# 14_Power_DCIN.net
KiCad netlist of a schematic drawn in Altium Designer
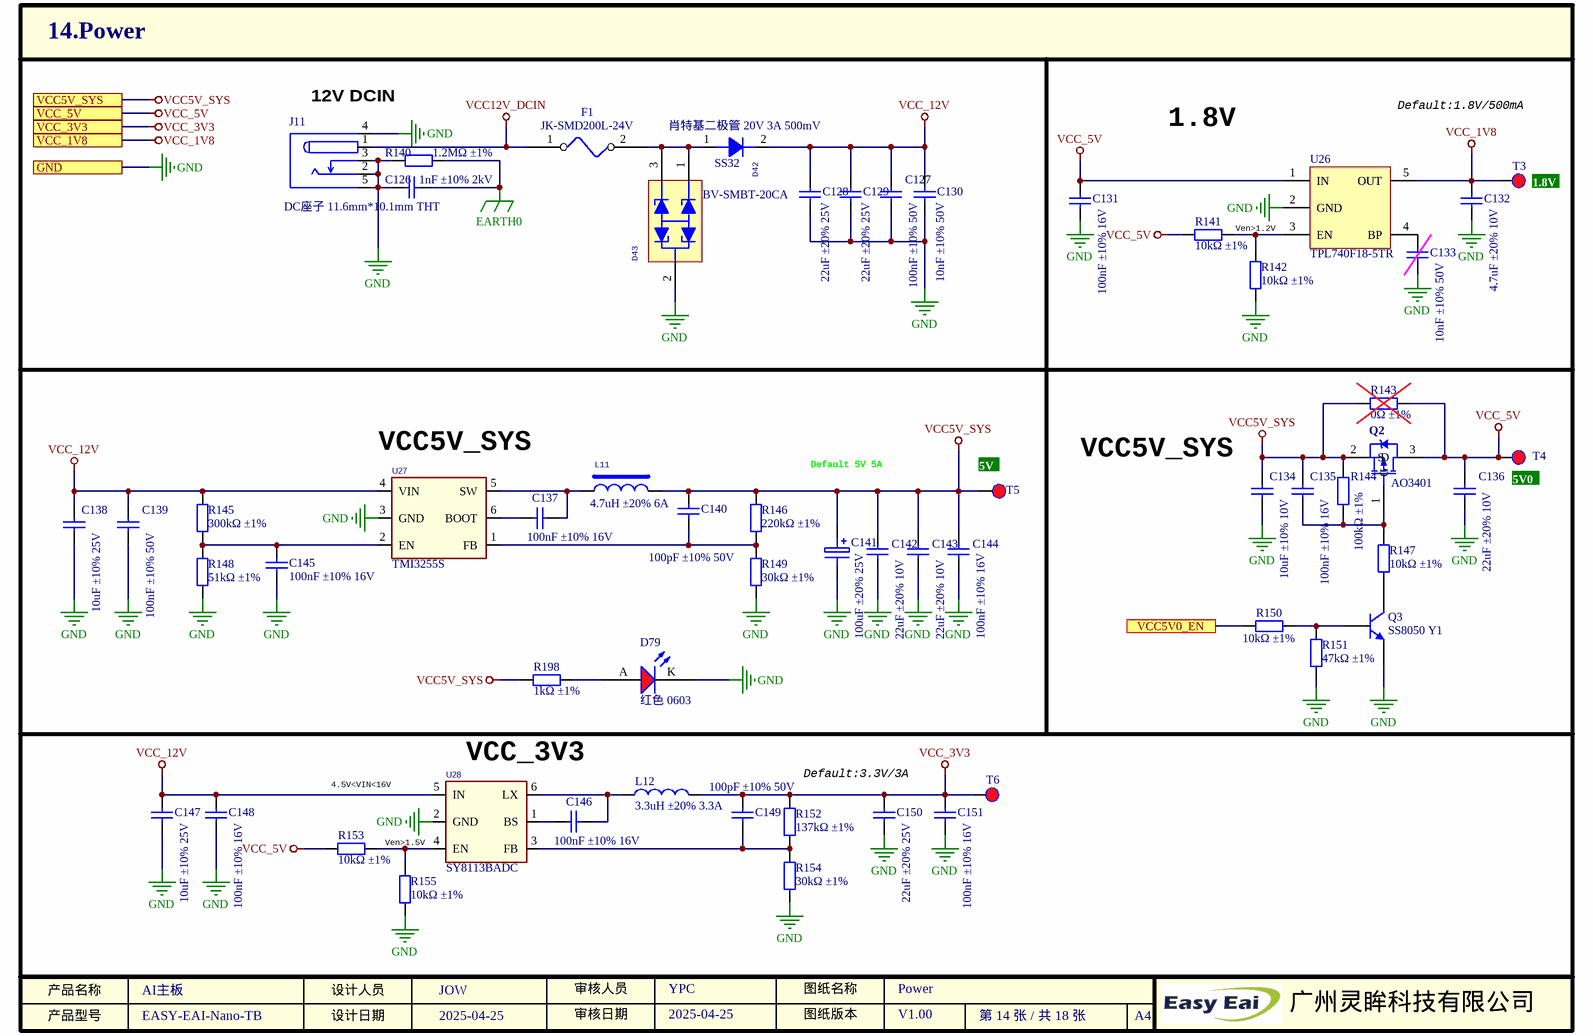
[diagram p0: 14.Power_DCIN.SchDoc]

(export (version "E")
  (design (tool "Eeschema 10.0.6"))
  (components
    (comp (ref "C126")
      (value "CC1206KKX7RDBB102")
      (footprint "1206_C")
      (description "SPZL000332")
      (fields (field (name "描述") "1nF ±10% 2kV"))
      (libsource (lib "altium-import") (part "root_0_1206 1nF ±10% 2kV_"))
    )
    (comp (ref "C127")
      (value "CC0603KRX7R9BB104")
      (footprint "0603_C")
      (description "SPZL000386")
      (fields (field (name "描述") "100nF ±10% 50V"))
      (libsource (lib "altium-import") (part "root_1_0603 100nF ±10% 50V_"))
    )
    (comp (ref "C128")
      (value "GRM21BR61E226ME44L")
      (footprint "0805_C")
      (description "SPZL000267")
      (fields (field (name "描述") "22uF ±20% 25V"))
      (libsource (lib "CAP_EASY-EAI") (part "0805 22uF ±20% 25V"))
    )
    (comp (ref "C129")
      (value "GRM21BR61E226ME44L")
      (footprint "0805_C")
      (description "SPZL000267")
      (fields (field (name "描述") "22uF ±20% 25V"))
      (libsource (lib "CAP_EASY-EAI") (part "0805 22uF ±20% 25V"))
    )
    (comp (ref "C130")
      (value "CL05B103KB5NNNC")
      (footprint "0402_C")
      (description "SPZL000342")
      (fields (field (name "描述") "10nF ±10% 50V"))
      (libsource (lib "CAP_EASY-EAI") (part "0402 10nF ±10% 50V"))
    )
    (comp (ref "C131")
      (value "CL05B104KO5NNNC")
      (footprint "0402_C")
      (description "SPZL000259")
      (fields (field (name "描述") "100nF ±10% 16V"))
      (libsource (lib "altium-import") (part "root_1_0402 100nF ±10% 16V_"))
    )
    (comp (ref "C132")
      (value "CL05A475MP5NRNC")
      (footprint "0402_C")
      (description "SPZL000339")
      (fields (field (name "描述") "4.7uF ±20% 10V"))
      (libsource (lib "altium-import") (part "root_1_0402 4.7uF ±20% 10V_"))
    )
    (comp (ref "C133")
      (value "NC/CL05B103KB5NNNC")
      (footprint "0402_C")
      (description "SPZL000342")
      (fields (field (name "描述") "10nF ±10% 50V"))
      (libsource (lib "altium-import") (part "root_1_0402 10nF ±10% 50V_"))
    )
    (comp (ref "C134")
      (value "CL10A106KP8NNNC")
      (footprint "0603_C")
      (description "SPZL000260")
      (fields (field (name "描述") "10uF ±10% 10V"))
      (libsource (lib "CAP_lexing") (part "0603 10uF ±10% 10V"))
    )
    (comp (ref "C135")
      (value "CL05B104KO5NNNC")
      (footprint "0402_C")
      (description "SPZL000259")
      (fields (field (name "描述") "100nF ±10% 16V"))
      (libsource (lib "CAP_lexing") (part "0402 100nF ±10% 16V"))
    )
    (comp (ref "C136")
      (value "CL10A226MP8NUNE")
      (footprint "0603_C")
      (description "SPZL000315")
      (fields (field (name "描述") "22uF ±20% 10V"))
      (libsource (lib "CAP_lexing") (part "0603 22uF ±20% 10V"))
    )
    (comp (ref "C137")
      (value "CL05B104KO5NNNC")
      (footprint "0402_C")
      (description "SPZL000259")
      (fields (field (name "描述") "100nF ±10% 16V"))
      (libsource (lib "altium-import") (part "root_0_0402 100nF ±10% 16V_"))
    )
    (comp (ref "C138")
      (value "GRM21BR61E106KA73L")
      (footprint "0805_C")
      (description "SPZL000262")
      (fields (field (name "描述") "10uF ±10% 25V"))
      (libsource (lib "altium-import") (part "root_1_0805 10uF ±10% 25V_"))
    )
    (comp (ref "C139")
      (value "CC0603KRX7R9BB104")
      (footprint "0603_C")
      (description "SPZL000386")
      (fields (field (name "描述") "100nF ±10% 50V"))
      (libsource (lib "altium-import") (part "root_1_0603 100nF ±10% 50V_"))
    )
    (comp (ref "C140")
      (value "CC0402KRX7R9BB101")
      (footprint "0402_C")
      (description "SPZL000312")
      (fields (field (name "描述") "100pF ±10% 50V"))
      (libsource (lib "altium-import") (part "root_1_0402 100pF ±10% 50V_"))
    )
    (comp (ref "C141")
      (value "RVT1E101M0607")
      (footprint "SMD,D6.3xL7.7mm")
      (description "SPZL000519")
      (fields (field (name "描述") "100uF ±20% 25V"))
      (libsource (lib "altium-import") (part "root_0_电解电容 100uF ±20% 25V_"))
    )
    (comp (ref "C142")
      (value "CL10A226MP8NUNE")
      (footprint "0603_C")
      (description "SPZL000315")
      (fields (field (name "描述") "22uF ±20% 10V"))
      (libsource (lib "altium-import") (part "root_1_0603 22uF ±20% 10V_"))
    )
    (comp (ref "C143")
      (value "CL10A226MP8NUNE")
      (footprint "0603_C")
      (description "SPZL000315")
      (fields (field (name "描述") "22uF ±20% 10V"))
      (libsource (lib "altium-import") (part "root_1_0603 22uF ±20% 10V_"))
    )
    (comp (ref "C144")
      (value "CL05B104KO5NNNC")
      (footprint "0402_C")
      (description "SPZL000259")
      (fields (field (name "描述") "100nF ±10% 16V"))
      (libsource (lib "altium-import") (part "root_1_0402 100nF ±10% 16V_"))
    )
    (comp (ref "C145")
      (value "CL05B104KO5NNNC")
      (footprint "0402_C")
      (description "SPZL000259")
      (fields (field (name "描述") "100nF ±10% 16V"))
      (libsource (lib "altium-import") (part "root_1_0402 100nF ±10% 16V_"))
    )
    (comp (ref "C146")
      (value "CL05B104KO5NNNC")
      (footprint "0402_C")
      (description "SPZL000259")
      (fields (field (name "描述") "100nF ±10% 16V"))
      (libsource (lib "altium-import") (part "root_0_0402 100nF ±10% 16V_"))
    )
    (comp (ref "C147")
      (value "GRM21BR61E106KA73L")
      (footprint "0805_C")
      (description "SPZL000262")
      (fields (field (name "描述") "10uF ±10% 25V"))
      (libsource (lib "altium-import") (part "root_1_0805 10uF ±10% 25V_"))
    )
    (comp (ref "C148")
      (value "CL05B104KO5NNNC")
      (footprint "0402_C")
      (description "SPZL000259")
      (fields (field (name "描述") "100nF ±10% 16V"))
      (libsource (lib "altium-import") (part "root_1_0402 100nF ±10% 16V_"))
    )
    (comp (ref "C149")
      (value "CC0402KRX7R9BB101")
      (footprint "0402_C")
      (description "SPZL000312")
      (fields (field (name "描述") "100pF ±10% 50V"))
      (libsource (lib "altium-import") (part "root_1_0402 100pF ±10% 50V_"))
    )
    (comp (ref "C150")
      (value "GRM21BR61E226ME44L")
      (footprint "0805_C")
      (description "SPZL000267")
      (fields (field (name "描述") "22uF ±20% 25V"))
      (libsource (lib "altium-import") (part "root_1_0805 22uF ±20% 25V_"))
    )
    (comp (ref "C151")
      (value "CL05B104KO5NNNC")
      (footprint "0402_C")
      (description "SPZL000259")
      (fields (field (name "描述") "100nF ±10% 16V"))
      (libsource (lib "altium-import") (part "root_1_0402 100nF ±10% 16V_"))
    )
    (comp (ref "D42")
      (value "肖特基二极管")
      (footprint "DO_214AC")
      (description "SPZL000094")
      (fields (field (name "描述") "肖特基二极管 20V 3A 500mV") (field (name "型号") "SS32"))
      (libsource (lib "Diode_EASY-EAI") (part "SS32"))
    )
    (comp (ref "D43")
      (value "BV-SMBT-20CA")
      (footprint "SMB-T_L5.4-W3.3-BI")
      (description "SPZL000611")
      (fields (field (name "型号") "BV-SMBT-20CA"))
      (libsource (lib "ESD_EASY-EAI") (part "TVS BV-SMBT-20CA"))
    )
    (comp (ref "D79")
      (value "红色 0603")
      (footprint "0603_LED_S1")
      (description "SPZL000214")
      (fields (field (name "描述") "红色 0603"))
      (libsource (lib "LED_EASY-EAI") (part "红色 0603"))
    )
    (comp (ref "F1")
      (value "JK-SMD200L-24V")
      (footprint "2920")
      (description "SPZL000105")
      (fields (field (name "型号") "JK-SMD200L-24V"))
      (libsource (lib "ESD_lexing") (part "自恢复保险丝 JK-SMD200L-24V"))
    )
    (comp (ref "J11")
      (value "DC-044A-20A")
      (footprint "DC-044A-20A")
      (description "SPZL000133")
      (fields (field (name "描述") "DC座子 11.6mm*10.1mm THT"))
      (libsource (lib "altium-import") (part "root_0_DC座子 11.6mm*10.1mm THT_"))
    )
    (comp (ref "L11")
      (value "MWSA0603S-4R7MT")
      (footprint "IND-SMD_L7.0-W6.6")
      (description "SPZL001133")
      (fields (field (name "描述") "4.7uH ±20% 6A"))
      (libsource (lib "Inductor_EASY-EAI") (part "4.7uH ±20% 6A"))
    )
    (comp (ref "L12")
      (value "SMNR4030-3R3MT")
      (footprint "IND-4.0*4.0*3.0")
      (description "SPZL000206")
      (fields (field (name "描述") "3.3uH ±20% 3.3A"))
      (libsource (lib "Inductor_EASY-EAI") (part "3.3uH ±20% 3.3A"))
    )
    (comp (ref "Q2")
      (value "AO3401")
      (footprint "SOT-23")
      (description "SPZL000800")
      (fields (field (name "型号") "AO3401"))
      (libsource (lib "MOS_lexing") (part "P沟道 AO3401"))
    )
    (comp (ref "Q3")
      (value "SS8050 Y1")
      (footprint "SOT-23(SOT-23-3)")
      (description "SPZL000089")
      (fields (field (name "型号") "SS8050 Y1"))
      (libsource (lib "MOS_lexing") (part "NPN SS8050 Y1"))
    )
    (comp (ref "R140")
      (value "1206W4F1204T5E")
      (footprint "1206_R")
      (description "SPZL000388")
      (fields (field (name "描述") "1.2MΩ ±1%"))
      (libsource (lib "RES_EASY-EAI") (part "1206 1.2MΩ ±1%"))
    )
    (comp (ref "R141")
      (value "0402WGF1002TCE")
      (footprint "0402_R")
      (description "SPZL000271")
      (fields (field (name "描述") "10kΩ ±1%"))
      (libsource (lib "") (part "0402 10kΩ ±1%_1"))
    )
    (comp (ref "R142")
      (value "0402WGF1002TCE")
      (footprint "0402_R")
      (description "SPZL000271")
      (fields (field (name "描述") "10kΩ ±1%"))
      (libsource (lib "RES_EASY-EAI") (part "0402 10kΩ ±1%"))
    )
    (comp (ref "R143")
      (value "NC/0805W8F0000T5E")
      (footprint "0805_R")
      (description "SPZL000350")
      (fields (field (name "描述") "0Ω ±1%"))
      (libsource (lib "RES_lexing") (part "0805 0Ω ±1%"))
    )
    (comp (ref "R144")
      (value "0402WGF1003TCE")
      (footprint "0402_R")
      (description "SPZL000282")
      (fields (field (name "描述") "100kΩ ±1%"))
      (libsource (lib "RES_lexing") (part "0402 100kΩ ±1%"))
    )
    (comp (ref "R145")
      (value "0402WGF3003TCE")
      (footprint "0402_R")
      (description "SPZL000393")
      (fields (field (name "描述") "300kΩ ±1%"))
      (libsource (lib "RES_EASY-EAI") (part "0402 300kΩ ±1%"))
    )
    (comp (ref "R146")
      (value "0402WGF2203TCE")
      (footprint "0402_R")
      (description "SPZL000877")
      (fields (field (name "描述") "220kΩ ±1%"))
      (libsource (lib "RES_EASY-EAI") (part "0402 220kΩ ±1%"))
    )
    (comp (ref "R147")
      (value "0402WGF1002TCE")
      (footprint "0402_R")
      (description "SPZL000271")
      (fields (field (name "描述") "10kΩ ±1%"))
      (libsource (lib "RES_lexing") (part "0402 10kΩ ±1%"))
    )
    (comp (ref "R148")
      (value "0402WGF5102TCE")
      (footprint "0402_R")
      (description "SPZL000788")
      (fields (field (name "描述") "51kΩ ±1%"))
      (libsource (lib "RES_EASY-EAI") (part "0402 51kΩ ±1%"))
    )
    (comp (ref "R149")
      (value "NQ02WGF3002TCE")
      (footprint "0402_R")
      (description "SPZL000323")
      (fields (field (name "描述") "30kΩ ±1%"))
      (libsource (lib "RES_EASY-EAI") (part "0402 30kΩ ±1%"))
    )
    (comp (ref "R150")
      (value "0402WGF1002TCE")
      (footprint "0402_R")
      (description "SPZL000271")
      (fields (field (name "描述") "10kΩ ±1%"))
      (libsource (lib "") (part "0402 10kΩ ±1%_1"))
    )
    (comp (ref "R151")
      (value "0402WGF4702TCE")
      (footprint "0402_R")
      (description "SPZL000348")
      (fields (field (name "描述") "47kΩ ±1%"))
      (libsource (lib "RES_lexing") (part "0402 47kΩ ±1%"))
    )
    (comp (ref "R152")
      (value "0402WGF1373TCE")
      (footprint "0402_R")
      (description "SPZL000322")
      (fields (field (name "描述") "137kΩ ±1%"))
      (libsource (lib "RES_EASY-EAI") (part "0402 137kΩ ±1%"))
    )
    (comp (ref "R153")
      (value "0402WGF1002TCE")
      (footprint "0402_R")
      (description "SPZL000271")
      (fields (field (name "描述") "10kΩ ±1%"))
      (libsource (lib "") (part "0402 10kΩ ±1%_1"))
    )
    (comp (ref "R154")
      (value "NQ02WGF3002TCE")
      (footprint "0402_R")
      (description "SPZL000323")
      (fields (field (name "描述") "30kΩ ±1%"))
      (libsource (lib "RES_EASY-EAI") (part "0402 30kΩ ±1%"))
    )
    (comp (ref "R155")
      (value "0402WGF1002TCE")
      (footprint "0402_R")
      (description "SPZL000271")
      (fields (field (name "描述") "10kΩ ±1%"))
      (libsource (lib "RES_EASY-EAI") (part "0402 10kΩ ±1%"))
    )
    (comp (ref "R198")
      (value "0402WGF1001TCE")
      (footprint "0402_R")
      (description "SPZL000275")
      (fields (field (name "描述") "1kΩ ±1%"))
      (libsource (lib "RES_EASY-EAI") (part "0402 1kΩ ±1%"))
    )
    (comp (ref "T3")
      (value "TEST-DOT")
      (footprint "PAD-25/40")
      (libsource (lib "Other_EASY-EAI") (part "TEST-DOT"))
    )
    (comp (ref "T4")
      (value "TEST-DOT")
      (footprint "PAD-25/40")
      (libsource (lib "Other_lexing") (part "TEST-DOT"))
    )
    (comp (ref "T5")
      (value "TEST-DOT")
      (footprint "PAD-25/40")
      (libsource (lib "Other_EASY-EAI") (part "TEST-DOT"))
    )
    (comp (ref "T6")
      (value "TEST-DOT")
      (footprint "PAD-25/40")
      (libsource (lib "Other_EASY-EAI") (part "TEST-DOT"))
    )
    (comp (ref "U26")
      (value "TPL740F18-5TR")
      (footprint "SOT-23-5")
      (description "SPZL000630")
      (fields (field (name "型号") "TPL740F18-5TR"))
      (libsource (lib "EASY-EAI-Nano-TB V1.01") (part "TPL740F18-5TR"))
    )
    (comp (ref "U27")
      (value "TMI3255S")
      (footprint "SOT23-6")
      (description "SPZL001130")
      (fields (field (name "型号") "TMI3255S"))
      (libsource (lib "Power_EASY-EAI") (part "TMI3255S"))
    )
    (comp (ref "U28")
      (value "SY8113BADC")
      (footprint "sot23-6")
      (description "SPZL000041")
      (fields (field (name "型号") "SY8113BADC"))
      (libsource (lib "Power_EASY-EAI") (part "SY8113BADC"))
    )
  )
  (nets
    (net (code "1") (name "/VCC5V0_EN") (class "Default")
      (node (ref "R150") (pin "1") (pinfunction "1_1") (pintype "passive"))
    )
    (net (code "2") (name "EARTH0") (class "Default")
      (node (ref "C126") (pin "2") (pinfunction "2_2") (pintype "passive"))
      (node (ref "R140") (pin "2") (pinfunction "2_2") (pintype "passive"))
    )
    (net (code "3") (name "GND") (class "Default")
      (node (ref "C126") (pin "1") (pinfunction "1_1") (pintype "passive"))
      (node (ref "C127") (pin "1") (pinfunction "1_1") (pintype "passive"))
      (node (ref "C128") (pin "1") (pinfunction "1_1") (pintype "passive"))
      (node (ref "C129") (pin "1") (pinfunction "1_1") (pintype "passive"))
      (node (ref "C130") (pin "1") (pinfunction "1_1") (pintype "passive"))
      (node (ref "C131") (pin "1") (pinfunction "1_1") (pintype "passive"))
      (node (ref "C132") (pin "1") (pinfunction "1_1") (pintype "passive"))
      (node (ref "C133") (pin "1") (pinfunction "1_1") (pintype "passive"))
      (node (ref "C134") (pin "1") (pinfunction "1_1") (pintype "passive"))
      (node (ref "C136") (pin "1") (pinfunction "1_1") (pintype "passive"))
      (node (ref "C138") (pin "1") (pinfunction "1_1") (pintype "passive"))
      (node (ref "C139") (pin "1") (pinfunction "1_1") (pintype "passive"))
      (node (ref "C141") (pin "2") (pinfunction "2_2") (pintype "passive"))
      (node (ref "C142") (pin "1") (pinfunction "1_1") (pintype "passive"))
      (node (ref "C143") (pin "1") (pinfunction "1_1") (pintype "passive"))
      (node (ref "C144") (pin "1") (pinfunction "1_1") (pintype "passive"))
      (node (ref "C145") (pin "1") (pinfunction "1_1") (pintype "passive"))
      (node (ref "C147") (pin "1") (pinfunction "1_1") (pintype "passive"))
      (node (ref "C148") (pin "1") (pinfunction "1_1") (pintype "passive"))
      (node (ref "C150") (pin "1") (pinfunction "1_1") (pintype "passive"))
      (node (ref "C151") (pin "1") (pinfunction "1_1") (pintype "passive"))
      (node (ref "D43") (pin "2") (pintype "passive"))
      (node (ref "D79") (pin "K") (pinfunction "K_K") (pintype "passive"))
      (node (ref "J11") (pin "2") (pinfunction "2_2") (pintype "power_in"))
      (node (ref "J11") (pin "3") (pinfunction "3_3") (pintype "power_in"))
      (node (ref "J11") (pin "4") (pinfunction "4_4") (pintype "power_in"))
      (node (ref "J11") (pin "5") (pinfunction "5_5") (pintype "power_in"))
      (node (ref "Q3") (pin "2") (pinfunction "E_2") (pintype "passive"))
      (node (ref "R140") (pin "1") (pinfunction "1_1") (pintype "passive"))
      (node (ref "R142") (pin "1") (pinfunction "1_1") (pintype "passive"))
      (node (ref "R148") (pin "1") (pinfunction "1_1") (pintype "passive"))
      (node (ref "R149") (pin "1") (pinfunction "1_1") (pintype "passive"))
      (node (ref "R151") (pin "1") (pinfunction "1_1") (pintype "passive"))
      (node (ref "R154") (pin "1") (pinfunction "1_1") (pintype "passive"))
      (node (ref "R155") (pin "1") (pinfunction "1_1") (pintype "passive"))
      (node (ref "U26") (pin "2") (pinfunction "GND_2") (pintype "passive"))
      (node (ref "U27") (pin "3") (pinfunction "GND_3") (pintype "passive"))
      (node (ref "U28") (pin "2") (pinfunction "GND_2") (pintype "passive"))
    )
    (net (code "4") (name "Net-(D42-A)") (class "Default")
      (node (ref "D42") (pin "1") (pinfunction "A_1") (pintype "passive"))
      (node (ref "D43") (pin "1") (pintype "passive"))
      (node (ref "D43") (pin "3") (pintype "passive"))
      (node (ref "F1") (pin "2") (pinfunction "2_2") (pintype "passive"))
    )
    (net (code "5") (name "Net-(D79-PadA)") (class "Default")
      (node (ref "D79") (pin "A") (pinfunction "A_A") (pintype "passive"))
      (node (ref "R198") (pin "2") (pinfunction "2_2") (pintype "passive"))
    )
    (net (code "6") (name "Net-(Q2-G)") (class "Default")
      (node (ref "C135") (pin "1") (pinfunction "1_1") (pintype "passive"))
      (node (ref "Q2") (pin "1") (pinfunction "G_1") (pintype "passive"))
      (node (ref "R144") (pin "1") (pinfunction "1_1") (pintype "passive"))
      (node (ref "R147") (pin "2") (pinfunction "2_2") (pintype "passive"))
    )
    (net (code "7") (name "Net-(Q3-B)") (class "Default")
      (node (ref "Q3") (pin "1") (pinfunction "B_1") (pintype "passive"))
      (node (ref "R150") (pin "2") (pinfunction "2_2") (pintype "passive"))
      (node (ref "R151") (pin "2") (pinfunction "2_2") (pintype "passive"))
    )
    (net (code "8") (name "Net-(Q3-C)") (class "Default")
      (node (ref "Q3") (pin "3") (pinfunction "C_3") (pintype "passive"))
      (node (ref "R147") (pin "1") (pinfunction "1_1") (pintype "passive"))
    )
    (net (code "9") (name "Net-(U26-BP)") (class "Default")
      (node (ref "C133") (pin "2") (pinfunction "2_2") (pintype "passive"))
      (node (ref "U26") (pin "4") (pinfunction "BP_4") (pintype "passive"))
    )
    (net (code "10") (name "Net-(U26-EN)") (class "Default")
      (node (ref "R141") (pin "2") (pinfunction "2_2") (pintype "passive"))
      (node (ref "R142") (pin "2") (pinfunction "2_2") (pintype "passive"))
      (node (ref "U26") (pin "3") (pinfunction "EN_3") (pintype "passive"))
    )
    (net (code "11") (name "Net-(U27-BOOT)") (class "Default")
      (node (ref "C137") (pin "1") (pinfunction "1_1") (pintype "passive"))
      (node (ref "U27") (pin "6") (pinfunction "BOOT_6") (pintype "passive"))
    )
    (net (code "12") (name "Net-(U27-EN)") (class "Default")
      (node (ref "C145") (pin "2") (pinfunction "2_2") (pintype "passive"))
      (node (ref "R145") (pin "1") (pinfunction "1_1") (pintype "passive"))
      (node (ref "R148") (pin "2") (pinfunction "2_2") (pintype "passive"))
      (node (ref "U27") (pin "2") (pinfunction "EN_2") (pintype "passive"))
    )
    (net (code "13") (name "Net-(U27-FB)") (class "Default")
      (node (ref "C140") (pin "1") (pinfunction "1_1") (pintype "passive"))
      (node (ref "R146") (pin "1") (pinfunction "1_1") (pintype "passive"))
      (node (ref "R149") (pin "2") (pinfunction "2_2") (pintype "passive"))
      (node (ref "U27") (pin "1") (pinfunction "FB_1") (pintype "passive"))
    )
    (net (code "14") (name "Net-(U27-SW)") (class "Default")
      (node (ref "C137") (pin "2") (pinfunction "2_2") (pintype "passive"))
      (node (ref "L11") (pin "1") (pinfunction "1_1") (pintype "passive"))
      (node (ref "U27") (pin "5") (pinfunction "SW_5") (pintype "passive"))
    )
    (net (code "15") (name "Net-(U28-BS)") (class "Default")
      (node (ref "C146") (pin "1") (pinfunction "1_1") (pintype "passive"))
      (node (ref "U28") (pin "1") (pinfunction "BS_1") (pintype "passive"))
    )
    (net (code "16") (name "Net-(U28-EN)") (class "Default")
      (node (ref "R153") (pin "2") (pinfunction "2_2") (pintype "passive"))
      (node (ref "R155") (pin "2") (pinfunction "2_2") (pintype "passive"))
      (node (ref "U28") (pin "4") (pinfunction "EN_4") (pintype "passive"))
    )
    (net (code "17") (name "Net-(U28-FB)") (class "Default")
      (node (ref "C149") (pin "1") (pinfunction "1_1") (pintype "passive"))
      (node (ref "R152") (pin "1") (pinfunction "1_1") (pintype "passive"))
      (node (ref "R154") (pin "2") (pinfunction "2_2") (pintype "passive"))
      (node (ref "U28") (pin "3") (pinfunction "FB_3") (pintype "passive"))
    )
    (net (code "18") (name "Net-(U28-LX)") (class "Default")
      (node (ref "C146") (pin "2") (pinfunction "2_2") (pintype "passive"))
      (node (ref "L12") (pin "1") (pinfunction "1_1") (pintype "passive"))
      (node (ref "U28") (pin "6") (pinfunction "LX_6") (pintype "passive"))
    )
    (net (code "19") (name "VCC5V_SYS") (class "Default")
      (node (ref "C134") (pin "2") (pinfunction "2_2") (pintype "passive"))
      (node (ref "C135") (pin "2") (pinfunction "2_2") (pintype "passive"))
      (node (ref "C140") (pin "2") (pinfunction "2_2") (pintype "passive"))
      (node (ref "C141") (pin "1") (pinfunction "1_1") (pintype "passive"))
      (node (ref "C142") (pin "2") (pinfunction "2_2") (pintype "passive"))
      (node (ref "C143") (pin "2") (pinfunction "2_2") (pintype "passive"))
      (node (ref "C144") (pin "2") (pinfunction "2_2") (pintype "passive"))
      (node (ref "L11") (pin "2") (pinfunction "2_2") (pintype "passive"))
      (node (ref "Q2") (pin "2") (pinfunction "S_2") (pintype "passive"))
      (node (ref "R143") (pin "1") (pinfunction "1_1") (pintype "passive"))
      (node (ref "R144") (pin "2") (pinfunction "2_2") (pintype "passive"))
      (node (ref "R146") (pin "2") (pinfunction "2_2") (pintype "passive"))
      (node (ref "R198") (pin "1") (pinfunction "1_1") (pintype "passive"))
      (node (ref "T5") (pin "1") (pinfunction "1_1") (pintype "passive"))
    )
    (net (code "20") (name "VCC12V_DCIN") (class "Default")
      (node (ref "F1") (pin "1") (pinfunction "1_1") (pintype "passive"))
      (node (ref "J11") (pin "1") (pinfunction "1_1") (pintype "power_in"))
    )
    (net (code "21") (name "VCC_1V8") (class "Default")
      (node (ref "C132") (pin "2") (pinfunction "2_2") (pintype "passive"))
      (node (ref "T3") (pin "1") (pinfunction "1_1") (pintype "passive"))
      (node (ref "U26") (pin "5") (pinfunction "OUT_5") (pintype "passive"))
    )
    (net (code "22") (name "VCC_3V3") (class "Default")
      (node (ref "C149") (pin "2") (pinfunction "2_2") (pintype "passive"))
      (node (ref "C150") (pin "2") (pinfunction "2_2") (pintype "passive"))
      (node (ref "C151") (pin "2") (pinfunction "2_2") (pintype "passive"))
      (node (ref "L12") (pin "2") (pinfunction "2_2") (pintype "passive"))
      (node (ref "R152") (pin "2") (pinfunction "2_2") (pintype "passive"))
      (node (ref "T6") (pin "1") (pinfunction "1_1") (pintype "passive"))
    )
    (net (code "23") (name "VCC_5V") (class "Default")
      (node (ref "C131") (pin "2") (pinfunction "2_2") (pintype "passive"))
      (node (ref "C136") (pin "2") (pinfunction "2_2") (pintype "passive"))
      (node (ref "Q2") (pin "3") (pinfunction "D_3") (pintype "passive"))
      (node (ref "R141") (pin "1") (pinfunction "1_1") (pintype "passive"))
      (node (ref "R143") (pin "2") (pinfunction "2_2") (pintype "passive"))
      (node (ref "R153") (pin "1") (pinfunction "1_1") (pintype "passive"))
      (node (ref "T4") (pin "1") (pinfunction "1_1") (pintype "passive"))
      (node (ref "U26") (pin "1") (pinfunction "IN_1") (pintype "passive"))
    )
    (net (code "24") (name "VCC_12V") (class "Default")
      (node (ref "C127") (pin "2") (pinfunction "2_2") (pintype "passive"))
      (node (ref "C128") (pin "2") (pinfunction "2_2") (pintype "passive"))
      (node (ref "C129") (pin "2") (pinfunction "2_2") (pintype "passive"))
      (node (ref "C130") (pin "2") (pinfunction "2_2") (pintype "passive"))
      (node (ref "C138") (pin "2") (pinfunction "2_2") (pintype "passive"))
      (node (ref "C139") (pin "2") (pinfunction "2_2") (pintype "passive"))
      (node (ref "C147") (pin "2") (pinfunction "2_2") (pintype "passive"))
      (node (ref "C148") (pin "2") (pinfunction "2_2") (pintype "passive"))
      (node (ref "D42") (pin "2") (pinfunction "K_2") (pintype "passive"))
      (node (ref "R145") (pin "2") (pinfunction "2_2") (pintype "passive"))
      (node (ref "U27") (pin "4") (pinfunction "VIN_4") (pintype "passive"))
      (node (ref "U28") (pin "5") (pinfunction "IN_5") (pintype "passive"))
    )
  )
)
